# Sheet_1.net
KiCad netlist of a schematic drawn in EasyEDA
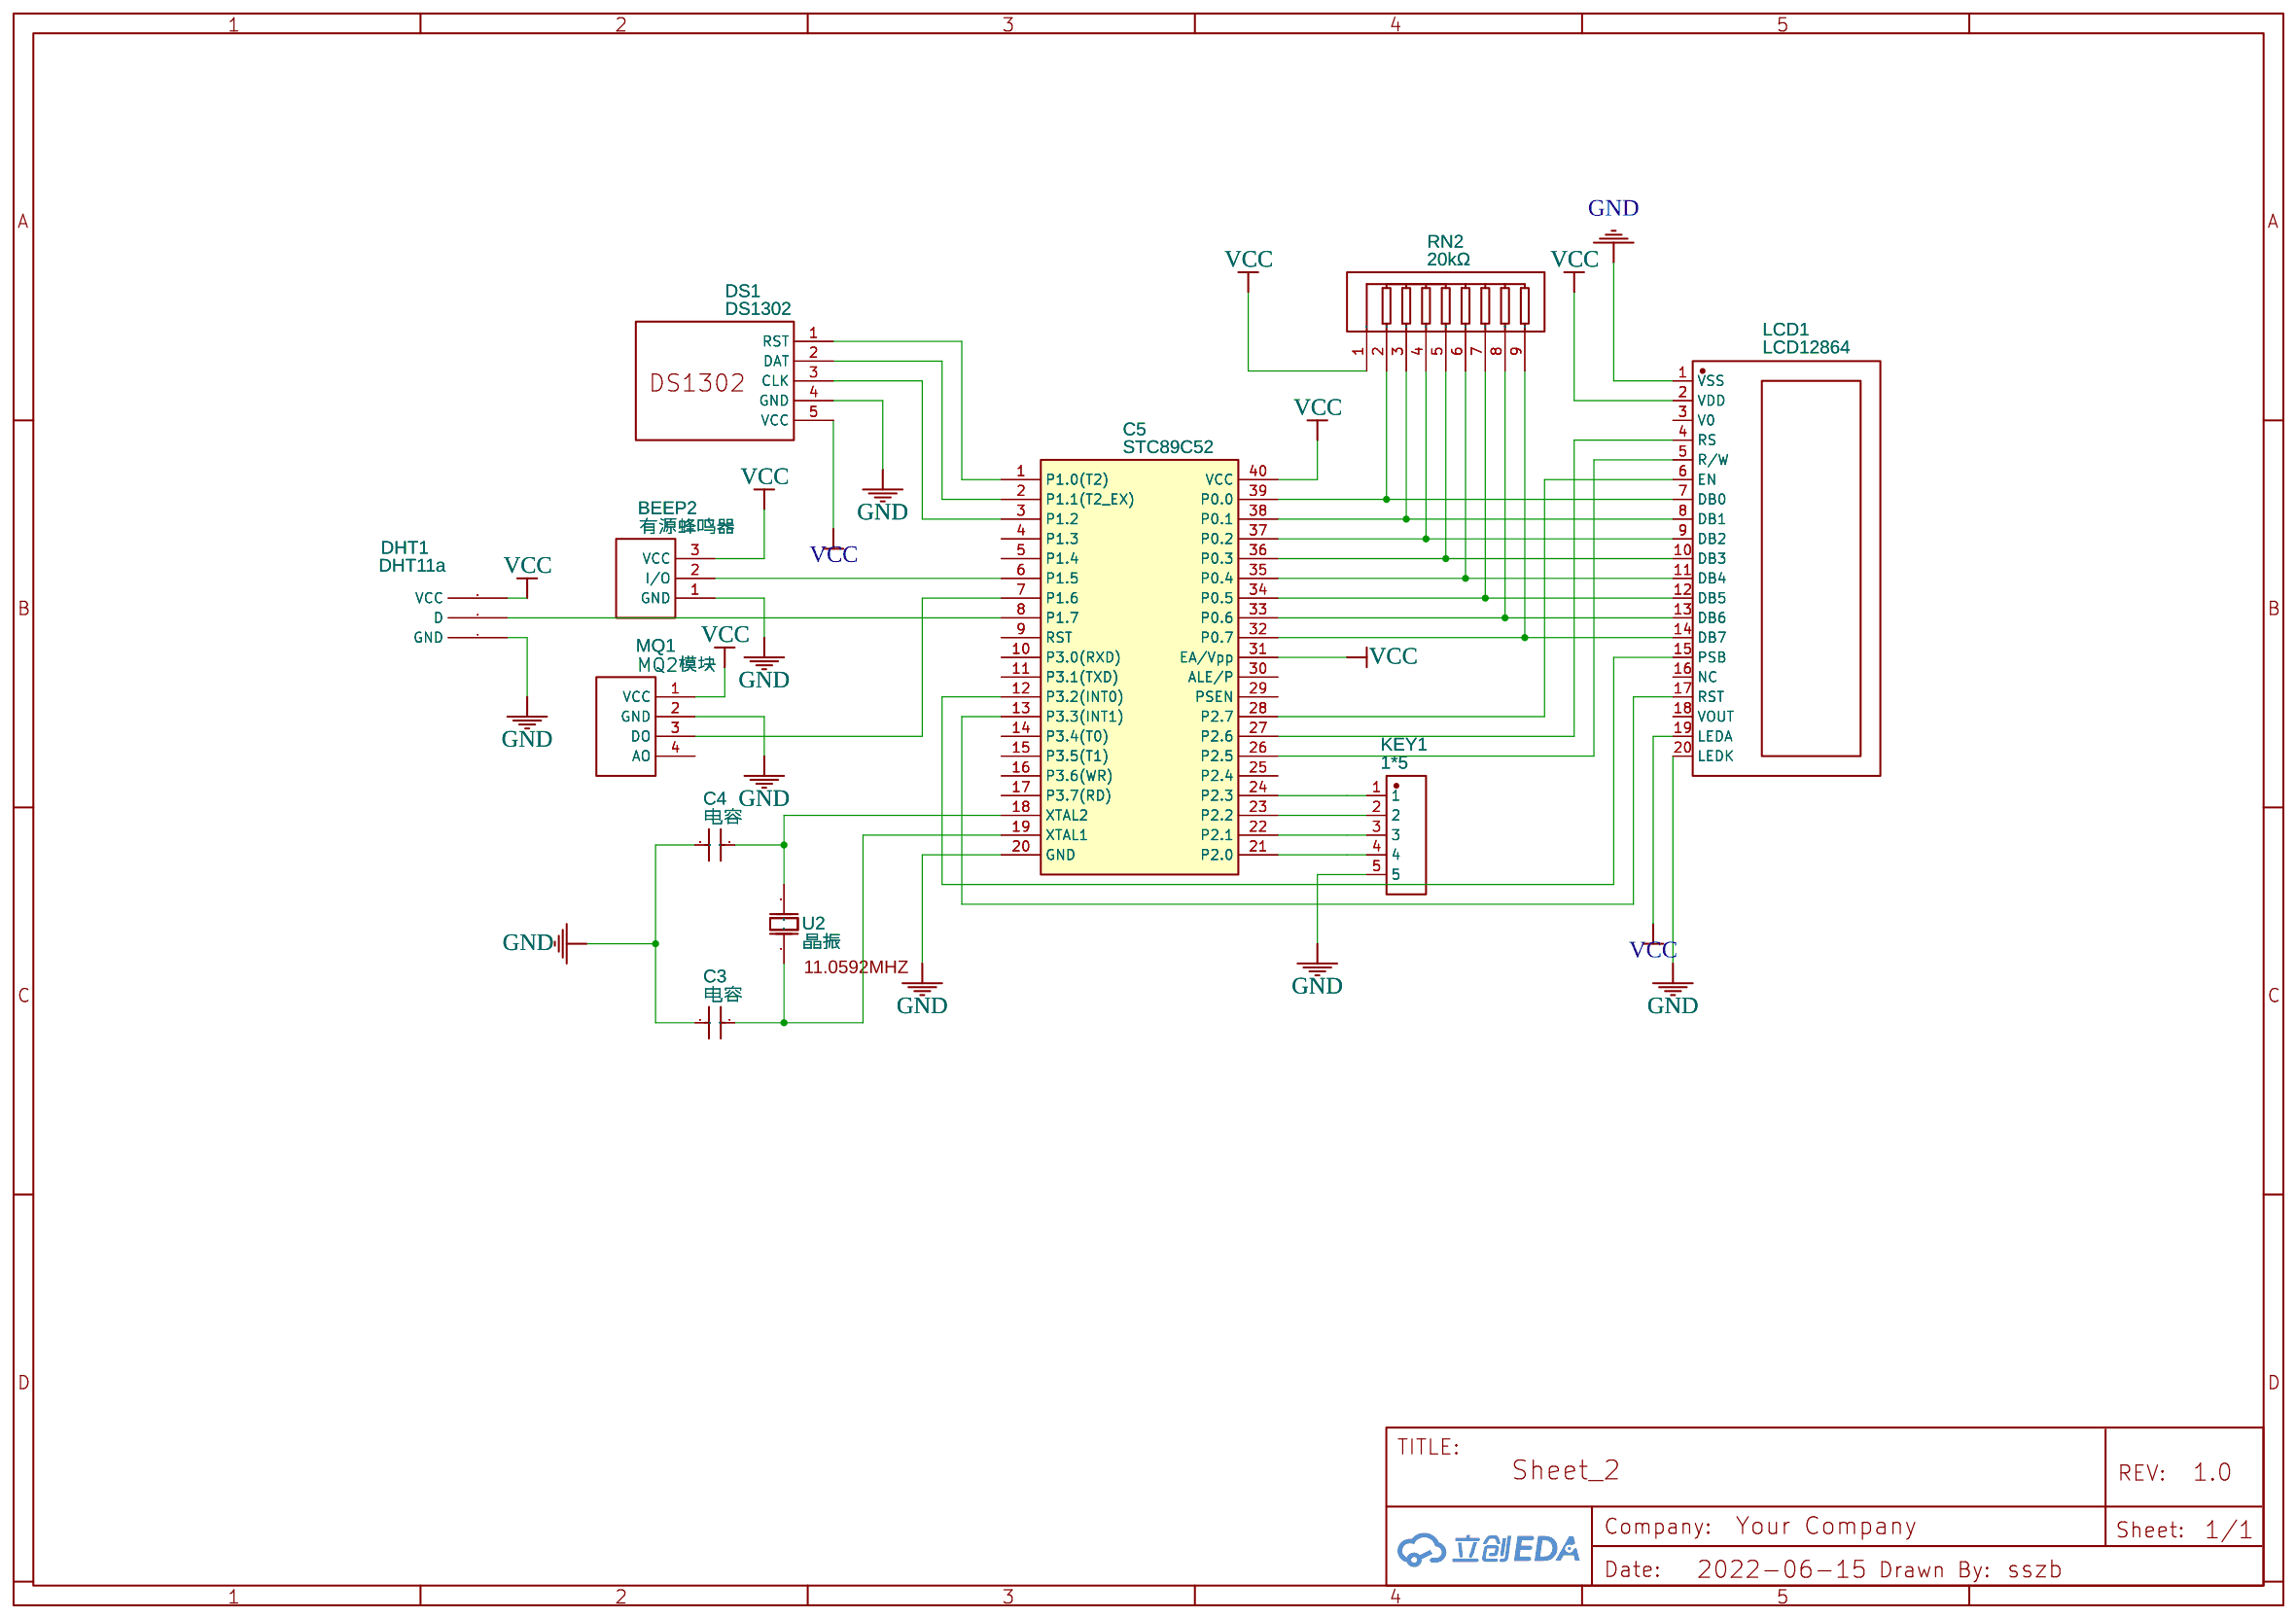
[diagram p0: schematic sheet]

(export (version "E")
  (design (tool "Eeschema 10.0.6"))
  (components
    (comp (ref "BEEP2") (value "有源蜂鸣器") (libsource (lib "") (part "有源蜂鸣器")))
    (comp (ref "C3") (value "电容") (libsource (lib "") (part "电容")))
    (comp (ref "C4") (value "电容") (libsource (lib "") (part "电容")))
    (comp (ref "C5") (value "STC89C52") (libsource (lib "") (part "STC89C52")))
    (comp (ref "DHT1")
      (value "DHT11a")
      (fields (field (name "BOM_Manufacturer Part") "模块DHT11开关模块模块DHT11度温湿湿度度传感器模块温湿"))
      (libsource (lib "") (part "温湿度传感器DHT11a"))
    )
    (comp (ref "DS1") (value "DS1302") (libsource (lib "") (part "DS1302")))
    (comp (ref "KEY1") (value "1*5") (libsource (lib "") (part "1*5")))
    (comp (ref "LCD1") (value "LCD12864") (libsource (lib "") (part "LCD12864")))
    (comp (ref "MQ1") (value "MQ2模块") (libsource (lib "") (part "MQ2模块")))
    (comp (ref "RN2")
      (value "20kΩ")
      (fields (field (name "BOM_Manufacturer Part") "A09-203JP") (field (name "BOM_Supplier Part") "C30847"))
      (libsource (lib "") (part "排阻"))
    )
    (comp (ref "U2") (value "晶振") (libsource (lib "") (part "晶振")))
  )
  (nets
    (net (code "1") (name "GND") (class "Default")
      (node (ref "BEEP2") (pin "1") (pinfunction "GND_1") (pintype "unspecified"))
      (node (ref "C3") (pin "1") (pinfunction "1_1") (pintype "unspecified"))
      (node (ref "C4") (pin "1") (pinfunction "1_1") (pintype "unspecified"))
      (node (ref "C5") (pin "20") (pinfunction "GND_20") (pintype "unspecified"))
      (node (ref "DHT1") (pin "1") (pinfunction "GND_1") (pintype "unspecified"))
      (node (ref "DS1") (pin "4") (pinfunction "GND_4") (pintype "unspecified"))
      (node (ref "KEY1") (pin "5") (pinfunction "5_5") (pintype "unspecified"))
      (node (ref "LCD1") (pin "1") (pinfunction "VSS_1") (pintype "unspecified"))
      (node (ref "LCD1") (pin "20") (pinfunction "LEDK_20") (pintype "unspecified"))
      (node (ref "MQ1") (pin "2") (pinfunction "GND_2") (pintype "unspecified"))
    )
    (net (code "2") (name "Net-(BEEP2-I{slash}O)") (class "Default")
      (node (ref "BEEP2") (pin "2") (pinfunction "I/O_2") (pintype "unspecified"))
      (node (ref "C5") (pin "6") (pinfunction "P1.5_6") (pintype "unspecified"))
    )
    (net (code "3") (name "Net-(C5-P0.0)") (class "Default")
      (node (ref "C5") (pin "39") (pinfunction "P0.0_39") (pintype "unspecified"))
      (node (ref "LCD1") (pin "7") (pinfunction "DB0_7") (pintype "unspecified"))
      (node (ref "RN2") (pin "2") (pinfunction "2_2") (pintype "unspecified"))
    )
    (net (code "4") (name "Net-(C5-P0.1)") (class "Default")
      (node (ref "C5") (pin "38") (pinfunction "P0.1_38") (pintype "unspecified"))
      (node (ref "LCD1") (pin "8") (pinfunction "DB1_8") (pintype "unspecified"))
      (node (ref "RN2") (pin "3") (pinfunction "3_3") (pintype "unspecified"))
    )
    (net (code "5") (name "Net-(C5-P0.2)") (class "Default")
      (node (ref "C5") (pin "37") (pinfunction "P0.2_37") (pintype "unspecified"))
      (node (ref "LCD1") (pin "9") (pinfunction "DB2_9") (pintype "unspecified"))
      (node (ref "RN2") (pin "4") (pinfunction "4_4") (pintype "unspecified"))
    )
    (net (code "6") (name "Net-(C5-P0.3)") (class "Default")
      (node (ref "C5") (pin "36") (pinfunction "P0.3_36") (pintype "unspecified"))
      (node (ref "LCD1") (pin "10") (pinfunction "DB3_10") (pintype "unspecified"))
      (node (ref "RN2") (pin "5") (pinfunction "5_5") (pintype "unspecified"))
    )
    (net (code "7") (name "Net-(C5-P0.4)") (class "Default")
      (node (ref "C5") (pin "35") (pinfunction "P0.4_35") (pintype "unspecified"))
      (node (ref "LCD1") (pin "11") (pinfunction "DB4_11") (pintype "unspecified"))
      (node (ref "RN2") (pin "6") (pinfunction "6_6") (pintype "unspecified"))
    )
    (net (code "8") (name "Net-(C5-P0.5)") (class "Default")
      (node (ref "C5") (pin "34") (pinfunction "P0.5_34") (pintype "unspecified"))
      (node (ref "LCD1") (pin "12") (pinfunction "DB5_12") (pintype "unspecified"))
      (node (ref "RN2") (pin "7") (pinfunction "7_7") (pintype "unspecified"))
    )
    (net (code "9") (name "Net-(C5-P0.6)") (class "Default")
      (node (ref "C5") (pin "33") (pinfunction "P0.6_33") (pintype "unspecified"))
      (node (ref "LCD1") (pin "13") (pinfunction "DB6_13") (pintype "unspecified"))
      (node (ref "RN2") (pin "8") (pinfunction "8_8") (pintype "unspecified"))
    )
    (net (code "10") (name "Net-(C5-P0.7)") (class "Default")
      (node (ref "C5") (pin "32") (pinfunction "P0.7_32") (pintype "unspecified"))
      (node (ref "LCD1") (pin "14") (pinfunction "DB7_14") (pintype "unspecified"))
      (node (ref "RN2") (pin "9") (pinfunction "9_9") (pintype "unspecified"))
    )
    (net (code "11") (name "Net-(C5-P1.0(T2))") (class "Default")
      (node (ref "C5") (pin "1") (pinfunction "P1.0(T2)_1") (pintype "unspecified"))
      (node (ref "DS1") (pin "1") (pinfunction "RST_1") (pintype "unspecified"))
    )
    (net (code "12") (name "Net-(C5-P1.1(T2_EX))") (class "Default")
      (node (ref "C5") (pin "2") (pinfunction "P1.1(T2_EX)_2") (pintype "unspecified"))
      (node (ref "DS1") (pin "2") (pinfunction "DAT_2") (pintype "unspecified"))
    )
    (net (code "13") (name "Net-(C5-P1.2)") (class "Default")
      (node (ref "C5") (pin "3") (pinfunction "P1.2_3") (pintype "unspecified"))
      (node (ref "DS1") (pin "3") (pinfunction "CLK_3") (pintype "unspecified"))
    )
    (net (code "14") (name "Net-(C5-P1.6)") (class "Default")
      (node (ref "C5") (pin "7") (pinfunction "P1.6_7") (pintype "unspecified"))
      (node (ref "MQ1") (pin "3") (pinfunction "DO_3") (pintype "unspecified"))
    )
    (net (code "15") (name "Net-(C5-P1.7)") (class "Default")
      (node (ref "C5") (pin "8") (pinfunction "P1.7_8") (pintype "unspecified"))
      (node (ref "DHT1") (pin "2") (pinfunction "D_2") (pintype "unspecified"))
    )
    (net (code "16") (name "Net-(C5-P2.0)") (class "Default")
      (node (ref "C5") (pin "21") (pinfunction "P2.0_21") (pintype "unspecified"))
      (node (ref "KEY1") (pin "4") (pinfunction "4_4") (pintype "unspecified"))
    )
    (net (code "17") (name "Net-(C5-P2.1)") (class "Default")
      (node (ref "C5") (pin "22") (pinfunction "P2.1_22") (pintype "unspecified"))
      (node (ref "KEY1") (pin "3") (pinfunction "3_3") (pintype "unspecified"))
    )
    (net (code "18") (name "Net-(C5-P2.2)") (class "Default")
      (node (ref "C5") (pin "23") (pinfunction "P2.2_23") (pintype "unspecified"))
      (node (ref "KEY1") (pin "2") (pinfunction "2_2") (pintype "unspecified"))
    )
    (net (code "19") (name "Net-(C5-P2.3)") (class "Default")
      (node (ref "C5") (pin "24") (pinfunction "P2.3_24") (pintype "unspecified"))
      (node (ref "KEY1") (pin "1") (pinfunction "1_1") (pintype "unspecified"))
    )
    (net (code "20") (name "Net-(C5-P2.5)") (class "Default")
      (node (ref "C5") (pin "26") (pinfunction "P2.5_26") (pintype "unspecified"))
      (node (ref "LCD1") (pin "5") (pinfunction "R/W_5") (pintype "unspecified"))
    )
    (net (code "21") (name "Net-(C5-P2.6)") (class "Default")
      (node (ref "C5") (pin "27") (pinfunction "P2.6_27") (pintype "unspecified"))
      (node (ref "LCD1") (pin "4") (pinfunction "RS_4") (pintype "unspecified"))
    )
    (net (code "22") (name "Net-(C5-P2.7)") (class "Default")
      (node (ref "C5") (pin "28") (pinfunction "P2.7_28") (pintype "unspecified"))
      (node (ref "LCD1") (pin "6") (pinfunction "EN_6") (pintype "unspecified"))
    )
    (net (code "23") (name "Net-(C5-P3.2(INT0))") (class "Default")
      (node (ref "C5") (pin "12") (pinfunction "P3.2(INT0)_12") (pintype "unspecified"))
      (node (ref "LCD1") (pin "15") (pinfunction "PSB_15") (pintype "unspecified"))
    )
    (net (code "24") (name "Net-(C5-P3.3(INT1))") (class "Default")
      (node (ref "C5") (pin "13") (pinfunction "P3.3(INT1)_13") (pintype "unspecified"))
      (node (ref "LCD1") (pin "17") (pinfunction "RST_17") (pintype "unspecified"))
    )
    (net (code "25") (name "Net-(C5-XTAL1)") (class "Default")
      (node (ref "C3") (pin "2") (pinfunction "2_2") (pintype "unspecified"))
      (node (ref "C5") (pin "19") (pinfunction "XTAL1_19") (pintype "unspecified"))
      (node (ref "U2") (pin "2") (pinfunction "OSC1_2") (pintype "input"))
    )
    (net (code "26") (name "Net-(C5-XTAL2)") (class "Default")
      (node (ref "C4") (pin "2") (pinfunction "2_2") (pintype "unspecified"))
      (node (ref "C5") (pin "18") (pinfunction "XTAL2_18") (pintype "unspecified"))
      (node (ref "U2") (pin "1") (pinfunction "OSC2_1") (pintype "input"))
    )
    (net (code "27") (name "VCC") (class "Default")
      (node (ref "BEEP2") (pin "3") (pinfunction "VCC_3") (pintype "unspecified"))
      (node (ref "C5") (pin "31") (pinfunction "EA/Vpp_31") (pintype "unspecified"))
      (node (ref "C5") (pin "40") (pinfunction "VCC_40") (pintype "unspecified"))
      (node (ref "DHT1") (pin "3") (pinfunction "VCC_3") (pintype "unspecified"))
      (node (ref "DS1") (pin "5") (pinfunction "VCC_5") (pintype "unspecified"))
      (node (ref "LCD1") (pin "19") (pinfunction "LEDA_19") (pintype "unspecified"))
      (node (ref "LCD1") (pin "2") (pinfunction "VDD_2") (pintype "unspecified"))
      (node (ref "MQ1") (pin "1") (pinfunction "VCC_1") (pintype "unspecified"))
      (node (ref "RN2") (pin "1") (pinfunction "1_1") (pintype "unspecified"))
    )
    (net (code "28") (name "unconnected-(C5-ALE{slash}P-Pad30)") (class "Default")
      (node (ref "C5") (pin "30") (pinfunction "ALE/P_30") (pintype "unspecified"))
    )
    (net (code "29") (name "unconnected-(C5-P1.3-Pad4)") (class "Default")
      (node (ref "C5") (pin "4") (pinfunction "P1.3_4") (pintype "unspecified"))
    )
    (net (code "30") (name "unconnected-(C5-P1.4-Pad5)") (class "Default")
      (node (ref "C5") (pin "5") (pinfunction "P1.4_5") (pintype "unspecified"))
    )
    (net (code "31") (name "unconnected-(C5-P2.4-Pad25)") (class "Default")
      (node (ref "C5") (pin "25") (pinfunction "P2.4_25") (pintype "unspecified"))
    )
    (net (code "32") (name "unconnected-(C5-P3.0(RXD)-Pad10)") (class "Default")
      (node (ref "C5") (pin "10") (pinfunction "P3.0(RXD)_10") (pintype "unspecified"))
    )
    (net (code "33") (name "unconnected-(C5-P3.1(TXD)-Pad11)") (class "Default")
      (node (ref "C5") (pin "11") (pinfunction "P3.1(TXD)_11") (pintype "unspecified"))
    )
    (net (code "34") (name "unconnected-(C5-P3.4(T0)-Pad14)") (class "Default")
      (node (ref "C5") (pin "14") (pinfunction "P3.4(T0)_14") (pintype "unspecified"))
    )
    (net (code "35") (name "unconnected-(C5-P3.5(T1)-Pad15)") (class "Default")
      (node (ref "C5") (pin "15") (pinfunction "P3.5(T1)_15") (pintype "unspecified"))
    )
    (net (code "36") (name "unconnected-(C5-P3.6(WR)-Pad16)") (class "Default")
      (node (ref "C5") (pin "16") (pinfunction "P3.6(WR)_16") (pintype "unspecified"))
    )
    (net (code "37") (name "unconnected-(C5-P3.7(RD)-Pad17)") (class "Default")
      (node (ref "C5") (pin "17") (pinfunction "P3.7(RD)_17") (pintype "unspecified"))
    )
    (net (code "38") (name "unconnected-(C5-PSEN-Pad29)") (class "Default")
      (node (ref "C5") (pin "29") (pinfunction "PSEN_29") (pintype "unspecified"))
    )
    (net (code "39") (name "unconnected-(C5-RST-Pad9)") (class "Default")
      (node (ref "C5") (pin "9") (pinfunction "RST_9") (pintype "unspecified"))
    )
    (net (code "40") (name "unconnected-(LCD1-NC-Pad16)") (class "Default")
      (node (ref "LCD1") (pin "16") (pinfunction "NC_16") (pintype "unspecified"))
    )
    (net (code "41") (name "unconnected-(LCD1-V0-Pad3)") (class "Default")
      (node (ref "LCD1") (pin "3") (pinfunction "V0_3") (pintype "unspecified"))
    )
    (net (code "42") (name "unconnected-(LCD1-VOUT-Pad18)") (class "Default")
      (node (ref "LCD1") (pin "18") (pinfunction "VOUT_18") (pintype "unspecified"))
    )
    (net (code "43") (name "unconnected-(MQ1-AO-Pad4)") (class "Default")
      (node (ref "MQ1") (pin "4") (pinfunction "AO_4") (pintype "unspecified"))
    )
  )
)
